# main.net
KiCad netlist of a schematic drawn in EAGLE
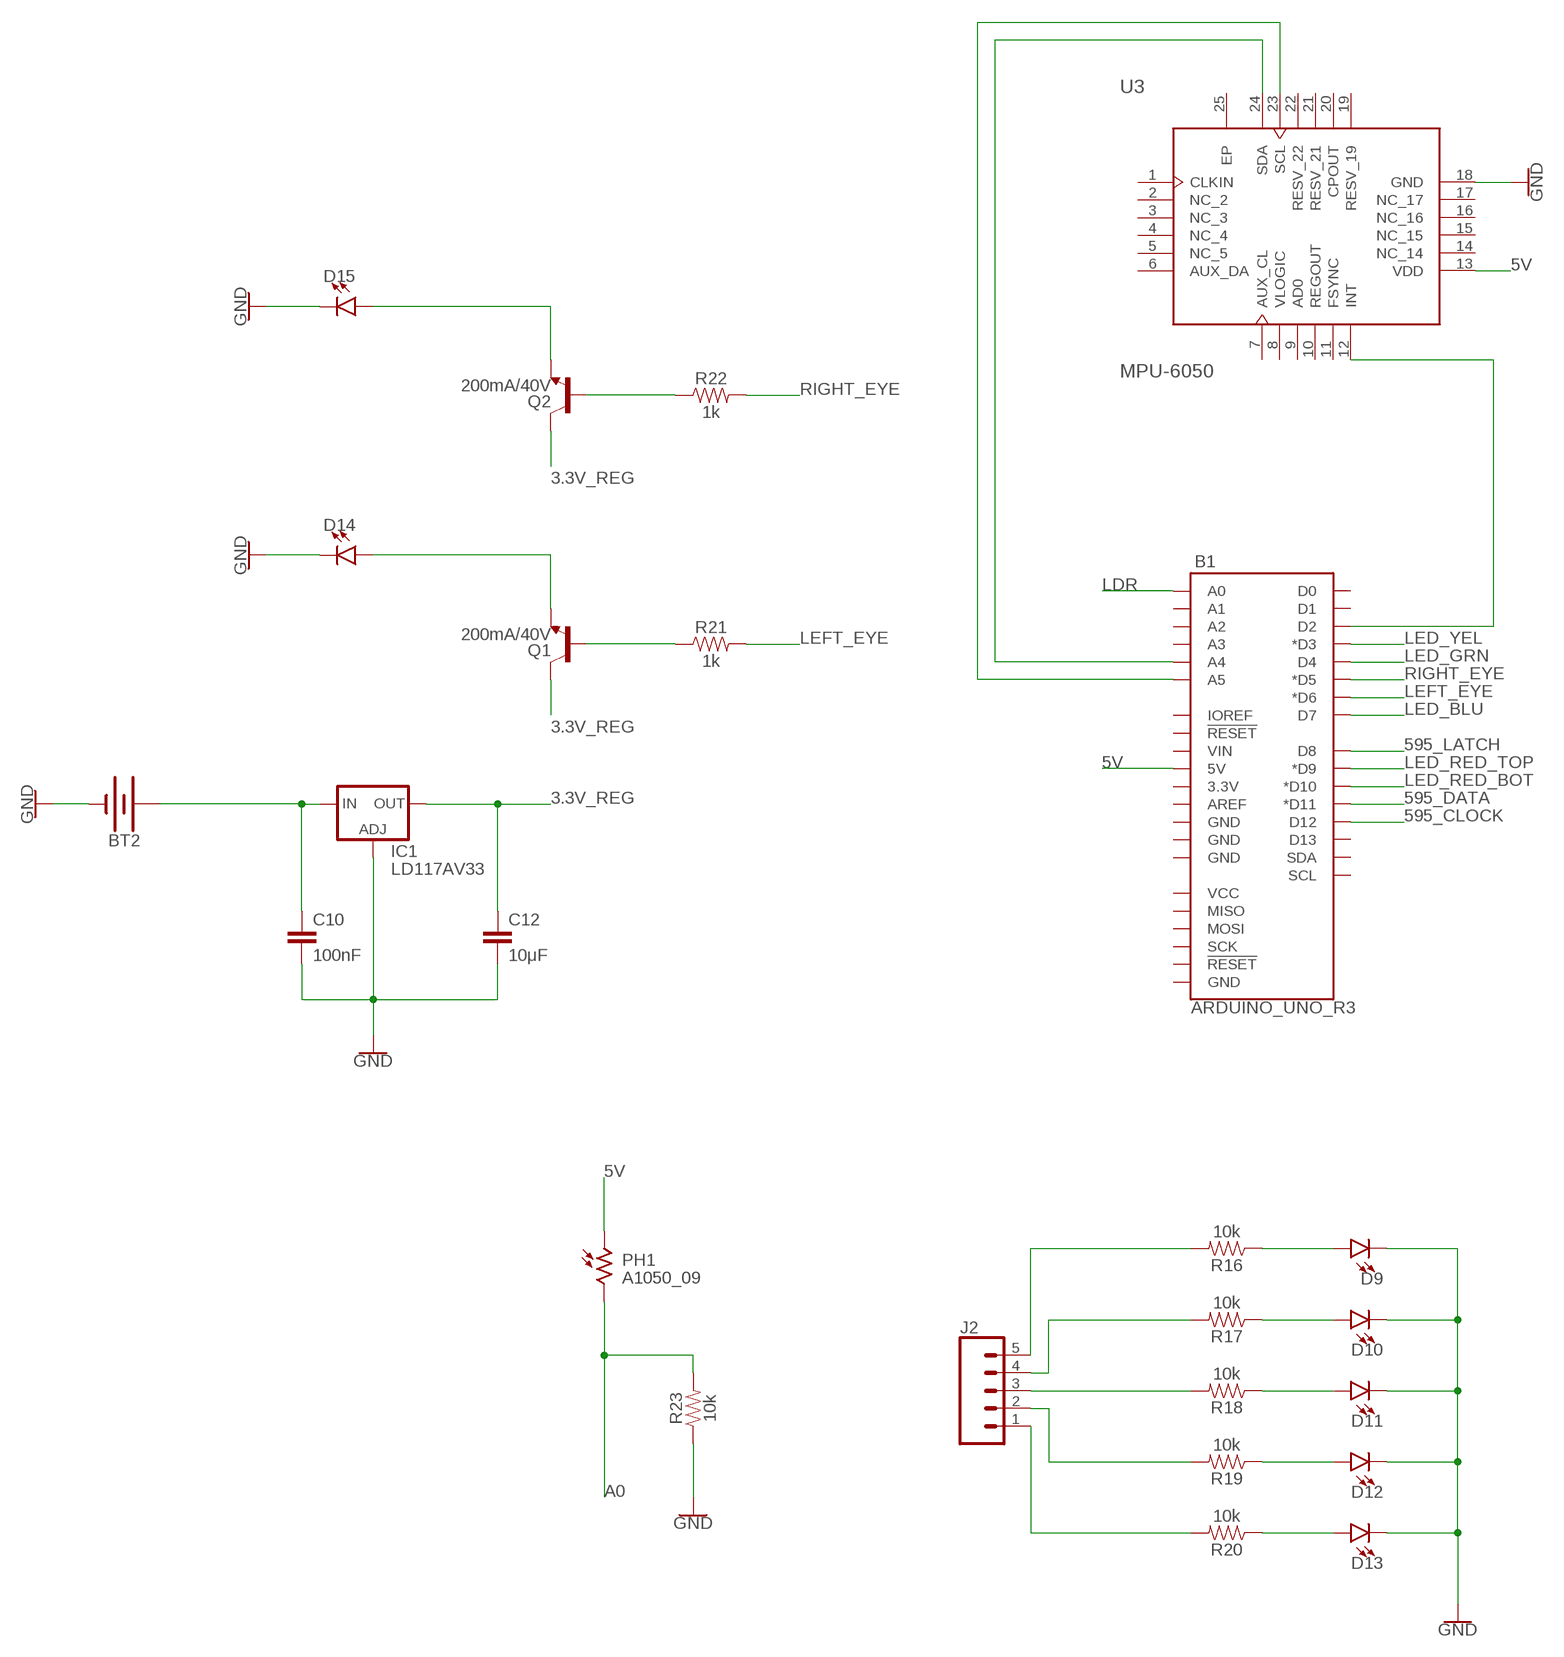
[diagram p0: schematic, sheet 1, part 1 of 2]
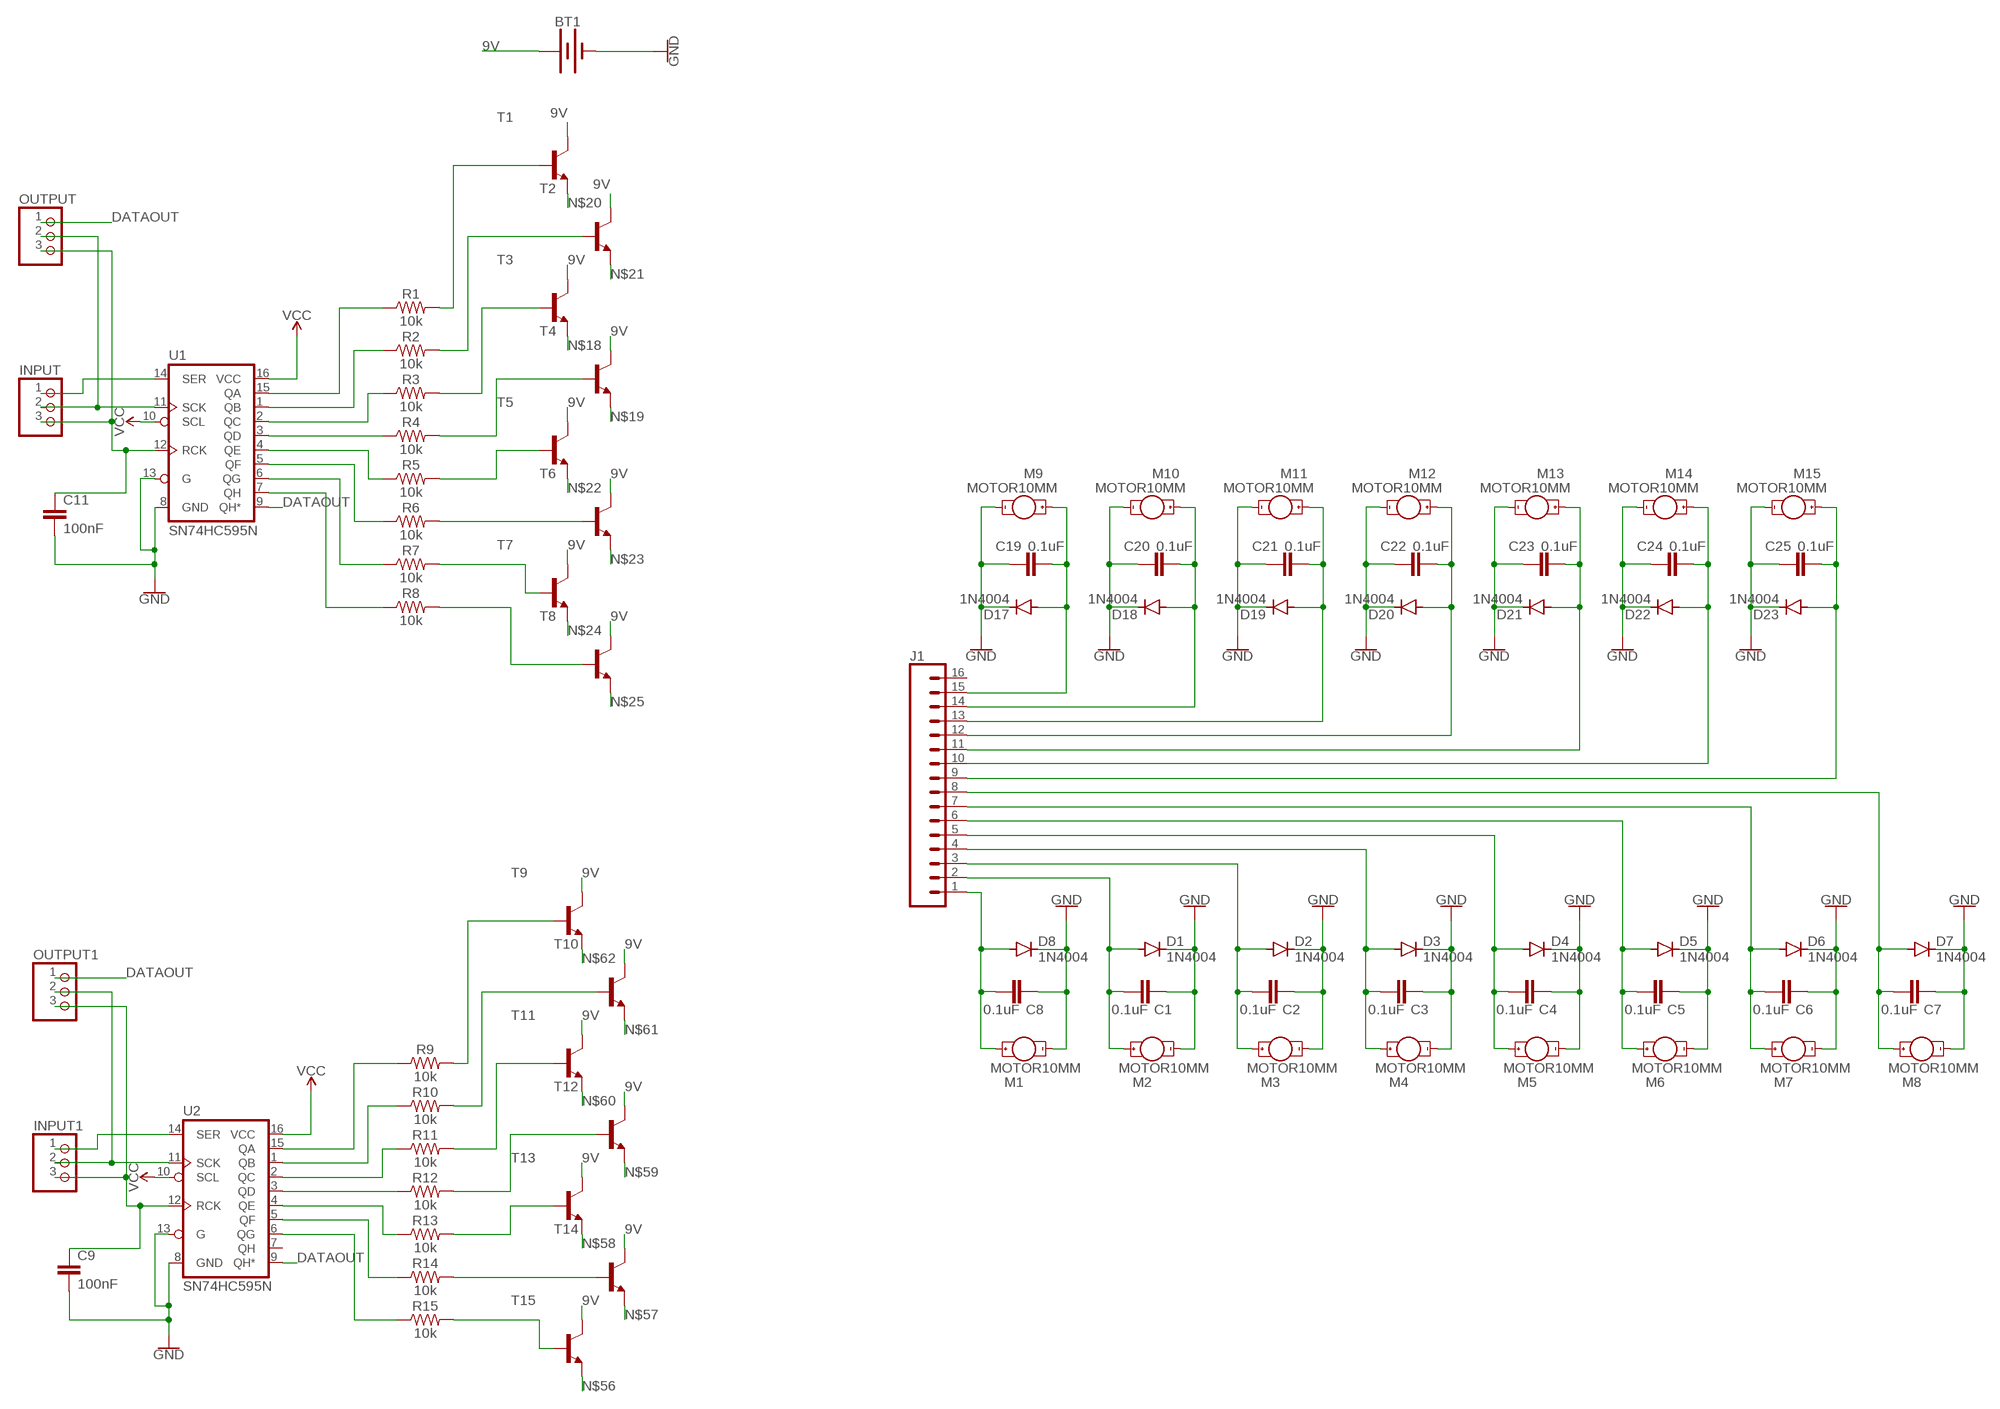
[diagram p1: schematic, sheet 1, part 2 of 2]

(export (version "E")
  (design (tool "Eeschema 10.0.6"))
  (components
    (comp (ref "B1")
      (value "ARDUINO_UNO_R3")
      (footprint "eagle-import:ARDUINO_R3")
      (libsource (lib "eagle-import") (part "ARDUINO_UNO_R3"))
    )
    (comp (ref "BT1")
      (value "BATTERY-9V")
      (footprint "eagle-import:BATTCON_9V")
      (libsource (lib "eagle-import") (part "BATTERY-9V"))
    )
    (comp (ref "BT2")
      (value "BATTERY-9V")
      (footprint "eagle-import:BATTCON_9V")
      (libsource (lib "eagle-import") (part "BATTERY-9V"))
    )
    (comp (ref "C1")
      (value "0.1uF")
      (footprint "eagle-import:CAP-PTH-SMALL-KIT")
      (libsource (lib "eagle-import") (part "0.1UF-KIT-EZ-50V-20%"))
    )
    (comp (ref "C2")
      (value "0.1uF")
      (footprint "eagle-import:CAP-PTH-SMALL-KIT")
      (libsource (lib "eagle-import") (part "0.1UF-KIT-EZ-50V-20%"))
    )
    (comp (ref "C3")
      (value "0.1uF")
      (footprint "eagle-import:CAP-PTH-SMALL-KIT")
      (libsource (lib "eagle-import") (part "0.1UF-KIT-EZ-50V-20%"))
    )
    (comp (ref "C4")
      (value "0.1uF")
      (footprint "eagle-import:CAP-PTH-SMALL-KIT")
      (libsource (lib "eagle-import") (part "0.1UF-KIT-EZ-50V-20%"))
    )
    (comp (ref "C5")
      (value "0.1uF")
      (footprint "eagle-import:CAP-PTH-SMALL-KIT")
      (libsource (lib "eagle-import") (part "0.1UF-KIT-EZ-50V-20%"))
    )
    (comp (ref "C6")
      (value "0.1uF")
      (footprint "eagle-import:CAP-PTH-SMALL-KIT")
      (libsource (lib "eagle-import") (part "0.1UF-KIT-EZ-50V-20%"))
    )
    (comp (ref "C7")
      (value "0.1uF")
      (footprint "eagle-import:CAP-PTH-SMALL-KIT")
      (libsource (lib "eagle-import") (part "0.1UF-KIT-EZ-50V-20%"))
    )
    (comp (ref "C8")
      (value "0.1uF")
      (footprint "eagle-import:CAP-PTH-SMALL-KIT")
      (libsource (lib "eagle-import") (part "0.1UF-KIT-EZ-50V-20%"))
    )
    (comp (ref "C9")
      (value "100nF")
      (footprint "eagle-import:CAP-PTH-10MM")
      (libsource (lib "eagle-import") (part "10NF-PTH-10MM-10000V-1-%"))
    )
    (comp (ref "C10")
      (value "100nF")
      (footprint "eagle-import:CAP-PTH-10MM")
      (libsource (lib "eagle-import") (part "10NF-PTH-10MM-10000V-1-%"))
    )
    (comp (ref "C11")
      (value "100nF")
      (footprint "eagle-import:CAP-PTH-10MM")
      (libsource (lib "eagle-import") (part "10NF-PTH-10MM-10000V-1-%"))
    )
    (comp (ref "C12")
      (value "10μF")
      (footprint "eagle-import:CAP-PTH-10MM")
      (libsource (lib "eagle-import") (part "10NF-PTH-10MM-10000V-1-%"))
    )
    (comp (ref "C19")
      (value "0.1uF")
      (footprint "eagle-import:CAP-PTH-SMALL-KIT")
      (libsource (lib "eagle-import") (part "0.1UF-KIT-EZ-50V-20%"))
    )
    (comp (ref "C20")
      (value "0.1uF")
      (footprint "eagle-import:CAP-PTH-SMALL-KIT")
      (libsource (lib "eagle-import") (part "0.1UF-KIT-EZ-50V-20%"))
    )
    (comp (ref "C21")
      (value "0.1uF")
      (footprint "eagle-import:CAP-PTH-SMALL-KIT")
      (libsource (lib "eagle-import") (part "0.1UF-KIT-EZ-50V-20%"))
    )
    (comp (ref "C22")
      (value "0.1uF")
      (footprint "eagle-import:CAP-PTH-SMALL-KIT")
      (libsource (lib "eagle-import") (part "0.1UF-KIT-EZ-50V-20%"))
    )
    (comp (ref "C23")
      (value "0.1uF")
      (footprint "eagle-import:CAP-PTH-SMALL-KIT")
      (libsource (lib "eagle-import") (part "0.1UF-KIT-EZ-50V-20%"))
    )
    (comp (ref "C24")
      (value "0.1uF")
      (footprint "eagle-import:CAP-PTH-SMALL-KIT")
      (libsource (lib "eagle-import") (part "0.1UF-KIT-EZ-50V-20%"))
    )
    (comp (ref "C25")
      (value "0.1uF")
      (footprint "eagle-import:CAP-PTH-SMALL-KIT")
      (libsource (lib "eagle-import") (part "0.1UF-KIT-EZ-50V-20%"))
    )
    (comp (ref "D1")
      (value "1N4004")
      (footprint "eagle-import:DO41-10")
      (libsource (lib "eagle-import") (part "1N4004"))
    )
    (comp (ref "D2")
      (value "1N4004")
      (footprint "eagle-import:DO41-10")
      (libsource (lib "eagle-import") (part "1N4004"))
    )
    (comp (ref "D3")
      (value "1N4004")
      (footprint "eagle-import:DO41-10")
      (libsource (lib "eagle-import") (part "1N4004"))
    )
    (comp (ref "D4")
      (value "1N4004")
      (footprint "eagle-import:DO41-10")
      (libsource (lib "eagle-import") (part "1N4004"))
    )
    (comp (ref "D5")
      (value "1N4004")
      (footprint "eagle-import:DO41-10")
      (libsource (lib "eagle-import") (part "1N4004"))
    )
    (comp (ref "D6")
      (value "1N4004")
      (footprint "eagle-import:DO41-10")
      (libsource (lib "eagle-import") (part "1N4004"))
    )
    (comp (ref "D7")
      (value "1N4004")
      (footprint "eagle-import:DO41-10")
      (libsource (lib "eagle-import") (part "1N4004"))
    )
    (comp (ref "D8")
      (value "1N4004")
      (footprint "eagle-import:DO41-10")
      (libsource (lib "eagle-import") (part "1N4004"))
    )
    (comp (ref "D9")
      (value "LED5MM")
      (footprint "eagle-import:LED_5MM")
      (libsource (lib "eagle-import") (part "LED5MM"))
    )
    (comp (ref "D10")
      (value "LED5MM")
      (footprint "eagle-import:LED_5MM")
      (libsource (lib "eagle-import") (part "LED5MM"))
    )
    (comp (ref "D11")
      (value "LED5MM")
      (footprint "eagle-import:LED_5MM")
      (libsource (lib "eagle-import") (part "LED5MM"))
    )
    (comp (ref "D12")
      (value "LED5MM")
      (footprint "eagle-import:LED_5MM")
      (libsource (lib "eagle-import") (part "LED5MM"))
    )
    (comp (ref "D13")
      (value "LED5MM")
      (footprint "eagle-import:LED_5MM")
      (libsource (lib "eagle-import") (part "LED5MM"))
    )
    (comp (ref "D14")
      (value "LED10MM")
      (footprint "eagle-import:LED_10MM")
      (libsource (lib "eagle-import") (part "LED10MM"))
    )
    (comp (ref "D15")
      (value "LED10MM")
      (footprint "eagle-import:LED_10MM")
      (libsource (lib "eagle-import") (part "LED10MM"))
    )
    (comp (ref "D17")
      (value "1N4004")
      (footprint "eagle-import:DO41-10")
      (libsource (lib "eagle-import") (part "1N4004"))
    )
    (comp (ref "D18")
      (value "1N4004")
      (footprint "eagle-import:DO41-10")
      (libsource (lib "eagle-import") (part "1N4004"))
    )
    (comp (ref "D19")
      (value "1N4004")
      (footprint "eagle-import:DO41-10")
      (libsource (lib "eagle-import") (part "1N4004"))
    )
    (comp (ref "D20")
      (value "1N4004")
      (footprint "eagle-import:DO41-10")
      (libsource (lib "eagle-import") (part "1N4004"))
    )
    (comp (ref "D21")
      (value "1N4004")
      (footprint "eagle-import:DO41-10")
      (libsource (lib "eagle-import") (part "1N4004"))
    )
    (comp (ref "D22")
      (value "1N4004")
      (footprint "eagle-import:DO41-10")
      (libsource (lib "eagle-import") (part "1N4004"))
    )
    (comp (ref "D23")
      (value "1N4004")
      (footprint "eagle-import:DO41-10")
      (libsource (lib "eagle-import") (part "1N4004"))
    )
    (comp (ref "IC1")
      (value "LD117AV33")
      (footprint "eagle-import:TO220L1")
      (libsource (lib "eagle-import") (part "LD117A?V33"))
    )
    (comp (ref "INPUT")
      (value "PINHD-1X3")
      (footprint "eagle-import:1X03")
      (libsource (lib "eagle-import") (part "PINHD-1X3"))
    )
    (comp (ref "INPUT1")
      (value "PINHD-1X3")
      (footprint "eagle-import:1X03")
      (libsource (lib "eagle-import") (part "PINHD-1X3"))
    )
    (comp (ref "J1")
      (value "CONN_16")
      (footprint "eagle-import:1X16")
      (libsource (lib "eagle-import") (part "CONN_16"))
    )
    (comp (ref "J2")
      (value "CONN_05")
      (footprint "eagle-import:1X05")
      (libsource (lib "eagle-import") (part "CONN_05"))
    )
    (comp (ref "M1")
      (value "MOTOR10MM")
      (footprint "eagle-import:VIBE-MOTOR-10MM")
      (libsource (lib "eagle-import") (part "MOTOR10MM"))
    )
    (comp (ref "M2")
      (value "MOTOR10MM")
      (footprint "eagle-import:VIBE-MOTOR-10MM")
      (libsource (lib "eagle-import") (part "MOTOR10MM"))
    )
    (comp (ref "M3")
      (value "MOTOR10MM")
      (footprint "eagle-import:VIBE-MOTOR-10MM")
      (libsource (lib "eagle-import") (part "MOTOR10MM"))
    )
    (comp (ref "M4")
      (value "MOTOR10MM")
      (footprint "eagle-import:VIBE-MOTOR-10MM")
      (libsource (lib "eagle-import") (part "MOTOR10MM"))
    )
    (comp (ref "M5")
      (value "MOTOR10MM")
      (footprint "eagle-import:VIBE-MOTOR-10MM")
      (libsource (lib "eagle-import") (part "MOTOR10MM"))
    )
    (comp (ref "M6")
      (value "MOTOR10MM")
      (footprint "eagle-import:VIBE-MOTOR-10MM")
      (libsource (lib "eagle-import") (part "MOTOR10MM"))
    )
    (comp (ref "M7")
      (value "MOTOR10MM")
      (footprint "eagle-import:VIBE-MOTOR-10MM")
      (libsource (lib "eagle-import") (part "MOTOR10MM"))
    )
    (comp (ref "M8")
      (value "MOTOR10MM")
      (footprint "eagle-import:VIBE-MOTOR-10MM")
      (libsource (lib "eagle-import") (part "MOTOR10MM"))
    )
    (comp (ref "M9")
      (value "MOTOR10MM")
      (footprint "eagle-import:VIBE-MOTOR-10MM")
      (libsource (lib "eagle-import") (part "MOTOR10MM"))
    )
    (comp (ref "M10")
      (value "MOTOR10MM")
      (footprint "eagle-import:VIBE-MOTOR-10MM")
      (libsource (lib "eagle-import") (part "MOTOR10MM"))
    )
    (comp (ref "M11")
      (value "MOTOR10MM")
      (footprint "eagle-import:VIBE-MOTOR-10MM")
      (libsource (lib "eagle-import") (part "MOTOR10MM"))
    )
    (comp (ref "M12")
      (value "MOTOR10MM")
      (footprint "eagle-import:VIBE-MOTOR-10MM")
      (libsource (lib "eagle-import") (part "MOTOR10MM"))
    )
    (comp (ref "M13")
      (value "MOTOR10MM")
      (footprint "eagle-import:VIBE-MOTOR-10MM")
      (libsource (lib "eagle-import") (part "MOTOR10MM"))
    )
    (comp (ref "M14")
      (value "MOTOR10MM")
      (footprint "eagle-import:VIBE-MOTOR-10MM")
      (libsource (lib "eagle-import") (part "MOTOR10MM"))
    )
    (comp (ref "M15")
      (value "MOTOR10MM")
      (footprint "eagle-import:VIBE-MOTOR-10MM")
      (libsource (lib "eagle-import") (part "MOTOR10MM"))
    )
    (comp (ref "OUTPUT")
      (value "PINHD-1X3")
      (footprint "eagle-import:1X03")
      (libsource (lib "eagle-import") (part "PINHD-1X3"))
    )
    (comp (ref "OUTPUT1")
      (value "PINHD-1X3")
      (footprint "eagle-import:1X03")
      (libsource (lib "eagle-import") (part "PINHD-1X3"))
    )
    (comp (ref "PH1")
      (value "A1050_09")
      (footprint "eagle-import:T0-46-A10XX")
      (libsource (lib "eagle-import") (part "A1050_09"))
    )
    (comp (ref "Q1")
      (value "200mA/40V")
      (footprint "eagle-import:TO-92")
      (libsource (lib "eagle-import") (part "TRANS_NPN-2N3904"))
    )
    (comp (ref "Q2")
      (value "200mA/40V")
      (footprint "eagle-import:TO-92")
      (libsource (lib "eagle-import") (part "TRANS_NPN-2N3904"))
    )
    (comp (ref "R1")
      (value "10k")
      (footprint "eagle-import:AXIAL-0.3")
      (libsource (lib "eagle-import") (part "10KOHM-HORIZ-1/4W-1%"))
    )
    (comp (ref "R2")
      (value "10k")
      (footprint "eagle-import:AXIAL-0.3")
      (libsource (lib "eagle-import") (part "10KOHM-HORIZ-1/4W-1%"))
    )
    (comp (ref "R3")
      (value "10k")
      (footprint "eagle-import:AXIAL-0.3")
      (libsource (lib "eagle-import") (part "10KOHM-HORIZ-1/4W-1%"))
    )
    (comp (ref "R4")
      (value "10k")
      (footprint "eagle-import:AXIAL-0.3")
      (libsource (lib "eagle-import") (part "10KOHM-HORIZ-1/4W-1%"))
    )
    (comp (ref "R5")
      (value "10k")
      (footprint "eagle-import:AXIAL-0.3")
      (libsource (lib "eagle-import") (part "10KOHM-HORIZ-1/4W-1%"))
    )
    (comp (ref "R6")
      (value "10k")
      (footprint "eagle-import:AXIAL-0.3")
      (libsource (lib "eagle-import") (part "10KOHM-HORIZ-1/4W-1%"))
    )
    (comp (ref "R7")
      (value "10k")
      (footprint "eagle-import:AXIAL-0.3")
      (libsource (lib "eagle-import") (part "10KOHM-HORIZ-1/4W-1%"))
    )
    (comp (ref "R8")
      (value "10k")
      (footprint "eagle-import:AXIAL-0.3")
      (libsource (lib "eagle-import") (part "10KOHM-HORIZ-1/4W-1%"))
    )
    (comp (ref "R9")
      (value "10k")
      (footprint "eagle-import:AXIAL-0.3")
      (libsource (lib "eagle-import") (part "10KOHM-HORIZ-1/4W-1%"))
    )
    (comp (ref "R10")
      (value "10k")
      (footprint "eagle-import:AXIAL-0.3")
      (libsource (lib "eagle-import") (part "10KOHM-HORIZ-1/4W-1%"))
    )
    (comp (ref "R11")
      (value "10k")
      (footprint "eagle-import:AXIAL-0.3")
      (libsource (lib "eagle-import") (part "10KOHM-HORIZ-1/4W-1%"))
    )
    (comp (ref "R12")
      (value "10k")
      (footprint "eagle-import:AXIAL-0.3")
      (libsource (lib "eagle-import") (part "10KOHM-HORIZ-1/4W-1%"))
    )
    (comp (ref "R13")
      (value "10k")
      (footprint "eagle-import:AXIAL-0.3")
      (libsource (lib "eagle-import") (part "10KOHM-HORIZ-1/4W-1%"))
    )
    (comp (ref "R14")
      (value "10k")
      (footprint "eagle-import:AXIAL-0.3")
      (libsource (lib "eagle-import") (part "10KOHM-HORIZ-1/4W-1%"))
    )
    (comp (ref "R15")
      (value "10k")
      (footprint "eagle-import:AXIAL-0.3")
      (libsource (lib "eagle-import") (part "10KOHM-HORIZ-1/4W-1%"))
    )
    (comp (ref "R16")
      (value "10k")
      (footprint "eagle-import:AXIAL-0.3")
      (libsource (lib "eagle-import") (part "10KOHM-HORIZ-1/4W-1%"))
    )
    (comp (ref "R17")
      (value "10k")
      (footprint "eagle-import:AXIAL-0.3")
      (libsource (lib "eagle-import") (part "10KOHM-HORIZ-1/4W-1%"))
    )
    (comp (ref "R18")
      (value "10k")
      (footprint "eagle-import:AXIAL-0.3")
      (libsource (lib "eagle-import") (part "10KOHM-HORIZ-1/4W-1%"))
    )
    (comp (ref "R19")
      (value "10k")
      (footprint "eagle-import:AXIAL-0.3")
      (libsource (lib "eagle-import") (part "10KOHM-HORIZ-1/4W-1%"))
    )
    (comp (ref "R20")
      (value "10k")
      (footprint "eagle-import:AXIAL-0.3")
      (libsource (lib "eagle-import") (part "10KOHM-HORIZ-1/4W-1%"))
    )
    (comp (ref "R21")
      (value "1k")
      (footprint "eagle-import:AXIAL-0.3")
      (libsource (lib "eagle-import") (part "1KOHM-HORIZ-1/4W-1%"))
    )
    (comp (ref "R22")
      (value "1k")
      (footprint "eagle-import:AXIAL-0.3")
      (libsource (lib "eagle-import") (part "1KOHM-HORIZ-1/4W-1%"))
    )
    (comp (ref "R23")
      (value "10k")
      (footprint "eagle-import:AXIAL-0.3")
      (libsource (lib "eagle-import") (part "10KOHM-HORIZ-1/4W-1%"))
    )
    (comp (ref "T1")
      (value "2N3904-NPN-TO92-EBC")
      (footprint "eagle-import:TO92-EBC")
      (libsource (lib "eagle-import") (part "-NPN-TO92-EBC2N3904"))
    )
    (comp (ref "T2")
      (value "2N3904-NPN-TO92-EBC")
      (footprint "eagle-import:TO92-EBC")
      (libsource (lib "eagle-import") (part "-NPN-TO92-EBC2N3904"))
    )
    (comp (ref "T3")
      (value "2N3904-NPN-TO92-EBC")
      (footprint "eagle-import:TO92-EBC")
      (libsource (lib "eagle-import") (part "-NPN-TO92-EBC2N3904"))
    )
    (comp (ref "T4")
      (value "2N3904-NPN-TO92-EBC")
      (footprint "eagle-import:TO92-EBC")
      (libsource (lib "eagle-import") (part "-NPN-TO92-EBC2N3904"))
    )
    (comp (ref "T5")
      (value "2N3904-NPN-TO92-EBC")
      (footprint "eagle-import:TO92-EBC")
      (libsource (lib "eagle-import") (part "-NPN-TO92-EBC2N3904"))
    )
    (comp (ref "T6")
      (value "2N3904-NPN-TO92-EBC")
      (footprint "eagle-import:TO92-EBC")
      (libsource (lib "eagle-import") (part "-NPN-TO92-EBC2N3904"))
    )
    (comp (ref "T7")
      (value "2N3904-NPN-TO92-EBC")
      (footprint "eagle-import:TO92-EBC")
      (libsource (lib "eagle-import") (part "-NPN-TO92-EBC2N3904"))
    )
    (comp (ref "T8")
      (value "2N3904-NPN-TO92-EBC")
      (footprint "eagle-import:TO92-EBC")
      (libsource (lib "eagle-import") (part "-NPN-TO92-EBC2N3904"))
    )
    (comp (ref "T9")
      (value "2N3904-NPN-TO92-EBC")
      (footprint "eagle-import:TO92-EBC")
      (libsource (lib "eagle-import") (part "-NPN-TO92-EBC2N3904"))
    )
    (comp (ref "T10")
      (value "2N3904-NPN-TO92-EBC")
      (footprint "eagle-import:TO92-EBC")
      (libsource (lib "eagle-import") (part "-NPN-TO92-EBC2N3904"))
    )
    (comp (ref "T11")
      (value "2N3904-NPN-TO92-EBC")
      (footprint "eagle-import:TO92-EBC")
      (libsource (lib "eagle-import") (part "-NPN-TO92-EBC2N3904"))
    )
    (comp (ref "T12")
      (value "2N3904-NPN-TO92-EBC")
      (footprint "eagle-import:TO92-EBC")
      (libsource (lib "eagle-import") (part "-NPN-TO92-EBC2N3904"))
    )
    (comp (ref "T13")
      (value "2N3904-NPN-TO92-EBC")
      (footprint "eagle-import:TO92-EBC")
      (libsource (lib "eagle-import") (part "-NPN-TO92-EBC2N3904"))
    )
    (comp (ref "T14")
      (value "2N3904-NPN-TO92-EBC")
      (footprint "eagle-import:TO92-EBC")
      (libsource (lib "eagle-import") (part "-NPN-TO92-EBC2N3904"))
    )
    (comp (ref "T15")
      (value "2N3904-NPN-TO92-EBC")
      (footprint "eagle-import:TO92-EBC")
      (libsource (lib "eagle-import") (part "-NPN-TO92-EBC2N3904"))
    )
    (comp (ref "U1")
      (value "SN74HC595N")
      (footprint "eagle-import:DIP16")
      (libsource (lib "eagle-import") (part "74595NHC"))
    )
    (comp (ref "U2")
      (value "SN74HC595N")
      (footprint "eagle-import:DIP16")
      (libsource (lib "eagle-import") (part "74595NHC"))
    )
    (comp (ref "U3")
      (value "MPU-6050")
      (footprint "eagle-import:24-VFQFN")
      (fields
        (field (name "DIGIKEY_PART_NUMBER") "1428-1007-1-ND")
        (field (name "MANUFACTURER") "TDK InvenSense")
        (field (name "CREATED_BY") "PCBLayout.com")
      )
      (libsource (lib "eagle-import") (part "MPU-6050"))
    )
  )
  (nets
    (net (code "1") (name "/3.3V_REG") (class "Default")
      (node (ref "C12") (pin "1") (pinfunction "1_1") (pintype "passive"))
      (node (ref "IC1") (pin "2") (pinfunction "OUT_2") (pintype "passive"))
      (node (ref "Q1") (pin "3") (pinfunction "C_3") (pintype "passive"))
      (node (ref "Q2") (pin "3") (pinfunction "C_3") (pintype "passive"))
    )
    (net (code "2") (name "/5V") (class "Default")
      (node (ref "B1") (pin "5V") (pinfunction "5V_5V") (pintype "bidirectional"))
      (node (ref "PH1") (pin "1") (pinfunction "1_1") (pintype "passive"))
      (node (ref "U3") (pin "13") (pinfunction "VDD_13") (pintype "power_in"))
    )
    (net (code "3") (name "/9V") (class "Default")
      (node (ref "BT1") (pin "+") (pinfunction "+_+") (pintype "power_in"))
      (node (ref "T1") (pin "C") (pinfunction "C_C") (pintype "passive"))
      (node (ref "T10") (pin "C") (pinfunction "C_C") (pintype "passive"))
      (node (ref "T11") (pin "C") (pinfunction "C_C") (pintype "passive"))
      (node (ref "T12") (pin "C") (pinfunction "C_C") (pintype "passive"))
      (node (ref "T13") (pin "C") (pinfunction "C_C") (pintype "passive"))
      (node (ref "T14") (pin "C") (pinfunction "C_C") (pintype "passive"))
      (node (ref "T15") (pin "C") (pinfunction "C_C") (pintype "passive"))
      (node (ref "T2") (pin "C") (pinfunction "C_C") (pintype "passive"))
      (node (ref "T3") (pin "C") (pinfunction "C_C") (pintype "passive"))
      (node (ref "T4") (pin "C") (pinfunction "C_C") (pintype "passive"))
      (node (ref "T5") (pin "C") (pinfunction "C_C") (pintype "passive"))
      (node (ref "T6") (pin "C") (pinfunction "C_C") (pintype "passive"))
      (node (ref "T7") (pin "C") (pinfunction "C_C") (pintype "passive"))
      (node (ref "T8") (pin "C") (pinfunction "C_C") (pintype "passive"))
      (node (ref "T9") (pin "C") (pinfunction "C_C") (pintype "passive"))
    )
    (net (code "4") (name "/595_CLOCK") (class "Default")
      (node (ref "B1") (pin "D12") (pinfunction "D12_D12") (pintype "bidirectional"))
    )
    (net (code "5") (name "/595_DATA") (class "Default")
      (node (ref "B1") (pin "D11") (pinfunction "*D11_D11") (pintype "bidirectional"))
    )
    (net (code "6") (name "/595_LATCH") (class "Default")
      (node (ref "B1") (pin "D8") (pinfunction "D8_D8") (pintype "bidirectional"))
    )
    (net (code "7") (name "/A0") (class "Default")
      (node (ref "PH1") (pin "2") (pinfunction "2_2") (pintype "passive"))
      (node (ref "R23") (pin "P$2") (pinfunction "2_P$2") (pintype "passive"))
    )
    (net (code "8") (name "/DATAOUT") (class "Default")
      (node (ref "OUTPUT") (pin "1") (pinfunction "1_1") (pintype "passive"))
      (node (ref "OUTPUT1") (pin "1") (pinfunction "1_1") (pintype "passive"))
      (node (ref "U1") (pin "9") (pinfunction "QH*_9") (pintype "tri_state"))
      (node (ref "U2") (pin "9") (pinfunction "QH*_9") (pintype "tri_state"))
    )
    (net (code "9") (name "/EP") (class "Default")
      (node (ref "U3") (pin "25") (pinfunction "EP_25") (pintype "power_in"))
    )
    (net (code "10") (name "/LDR") (class "Default")
      (node (ref "B1") (pin "A0") (pinfunction "A0_A0") (pintype "bidirectional"))
    )
    (net (code "11") (name "/LED_BLU") (class "Default")
      (node (ref "B1") (pin "D7") (pinfunction "D7_D7") (pintype "bidirectional"))
    )
    (net (code "12") (name "/LED_GRN") (class "Default")
      (node (ref "B1") (pin "D4") (pinfunction "D4_D4") (pintype "bidirectional"))
    )
    (net (code "13") (name "/LED_RED_BOT") (class "Default")
      (node (ref "B1") (pin "D10") (pinfunction "*D10_D10") (pintype "bidirectional"))
    )
    (net (code "14") (name "/LED_RED_TOP") (class "Default")
      (node (ref "B1") (pin "D9") (pinfunction "*D9_D9") (pintype "bidirectional"))
    )
    (net (code "15") (name "/LED_YEL") (class "Default")
      (node (ref "B1") (pin "D3") (pinfunction "*D3_D3") (pintype "bidirectional"))
    )
    (net (code "16") (name "/LEFT_EYE") (class "Default")
      (node (ref "B1") (pin "D6") (pinfunction "*D6_D6") (pintype "bidirectional"))
      (node (ref "R21") (pin "P$2") (pinfunction "2_P$2") (pintype "passive"))
    )
    (net (code "17") (name "/N$18") (class "Default")
      (node (ref "C2") (pin "2") (pinfunction "2_2") (pintype "passive"))
      (node (ref "D2") (pin "A") (pinfunction "A_A") (pintype "passive"))
      (node (ref "J1") (pin "3") (pinfunction "3_3") (pintype "passive"))
      (node (ref "M3") (pin "+") (pinfunction "+_+") (pintype "bidirectional"))
      (node (ref "T3") (pin "E") (pinfunction "E_E") (pintype "passive"))
    )
    (net (code "18") (name "/N$19") (class "Default")
      (node (ref "C3") (pin "2") (pinfunction "2_2") (pintype "passive"))
      (node (ref "D3") (pin "A") (pinfunction "A_A") (pintype "passive"))
      (node (ref "J1") (pin "4") (pinfunction "4_4") (pintype "passive"))
      (node (ref "M4") (pin "+") (pinfunction "+_+") (pintype "bidirectional"))
      (node (ref "T4") (pin "E") (pinfunction "E_E") (pintype "passive"))
    )
    (net (code "19") (name "/N$20") (class "Default")
      (node (ref "C8") (pin "2") (pinfunction "2_2") (pintype "passive"))
      (node (ref "D8") (pin "A") (pinfunction "A_A") (pintype "passive"))
      (node (ref "J1") (pin "1") (pinfunction "1_1") (pintype "passive"))
      (node (ref "M1") (pin "+") (pinfunction "+_+") (pintype "bidirectional"))
      (node (ref "T1") (pin "E") (pinfunction "E_E") (pintype "passive"))
    )
    (net (code "20") (name "/N$21") (class "Default")
      (node (ref "C1") (pin "2") (pinfunction "2_2") (pintype "passive"))
      (node (ref "D1") (pin "A") (pinfunction "A_A") (pintype "passive"))
      (node (ref "J1") (pin "2") (pinfunction "2_2") (pintype "passive"))
      (node (ref "M2") (pin "+") (pinfunction "+_+") (pintype "bidirectional"))
      (node (ref "T2") (pin "E") (pinfunction "E_E") (pintype "passive"))
    )
    (net (code "21") (name "/N$22") (class "Default")
      (node (ref "C4") (pin "2") (pinfunction "2_2") (pintype "passive"))
      (node (ref "D4") (pin "A") (pinfunction "A_A") (pintype "passive"))
      (node (ref "J1") (pin "5") (pinfunction "5_5") (pintype "passive"))
      (node (ref "M5") (pin "+") (pinfunction "+_+") (pintype "bidirectional"))
      (node (ref "T5") (pin "E") (pinfunction "E_E") (pintype "passive"))
    )
    (net (code "22") (name "/N$23") (class "Default")
      (node (ref "C5") (pin "2") (pinfunction "2_2") (pintype "passive"))
      (node (ref "D5") (pin "A") (pinfunction "A_A") (pintype "passive"))
      (node (ref "J1") (pin "6") (pinfunction "6_6") (pintype "passive"))
      (node (ref "M6") (pin "+") (pinfunction "+_+") (pintype "bidirectional"))
      (node (ref "T6") (pin "E") (pinfunction "E_E") (pintype "passive"))
    )
    (net (code "23") (name "/N$24") (class "Default")
      (node (ref "C6") (pin "2") (pinfunction "2_2") (pintype "passive"))
      (node (ref "D6") (pin "A") (pinfunction "A_A") (pintype "passive"))
      (node (ref "J1") (pin "7") (pinfunction "7_7") (pintype "passive"))
      (node (ref "M7") (pin "+") (pinfunction "+_+") (pintype "bidirectional"))
      (node (ref "T7") (pin "E") (pinfunction "E_E") (pintype "passive"))
    )
    (net (code "24") (name "/N$25") (class "Default")
      (node (ref "C7") (pin "2") (pinfunction "2_2") (pintype "passive"))
      (node (ref "D7") (pin "A") (pinfunction "A_A") (pintype "passive"))
      (node (ref "J1") (pin "8") (pinfunction "8_8") (pintype "passive"))
      (node (ref "M8") (pin "+") (pinfunction "+_+") (pintype "bidirectional"))
      (node (ref "T8") (pin "E") (pinfunction "E_E") (pintype "passive"))
    )
    (net (code "25") (name "/N$56") (class "Default")
      (node (ref "C19") (pin "2") (pinfunction "2_2") (pintype "passive"))
      (node (ref "D17") (pin "A") (pinfunction "A_A") (pintype "passive"))
      (node (ref "J1") (pin "15") (pinfunction "15_15") (pintype "passive"))
      (node (ref "M9") (pin "+") (pinfunction "+_+") (pintype "bidirectional"))
      (node (ref "T15") (pin "E") (pinfunction "E_E") (pintype "passive"))
    )
    (net (code "26") (name "/N$57") (class "Default")
      (node (ref "C20") (pin "2") (pinfunction "2_2") (pintype "passive"))
      (node (ref "D18") (pin "A") (pinfunction "A_A") (pintype "passive"))
      (node (ref "J1") (pin "14") (pinfunction "14_14") (pintype "passive"))
      (node (ref "M10") (pin "+") (pinfunction "+_+") (pintype "bidirectional"))
      (node (ref "T14") (pin "E") (pinfunction "E_E") (pintype "passive"))
    )
    (net (code "27") (name "/N$58") (class "Default")
      (node (ref "C21") (pin "2") (pinfunction "2_2") (pintype "passive"))
      (node (ref "D19") (pin "A") (pinfunction "A_A") (pintype "passive"))
      (node (ref "J1") (pin "13") (pinfunction "13_13") (pintype "passive"))
      (node (ref "M11") (pin "+") (pinfunction "+_+") (pintype "bidirectional"))
      (node (ref "T13") (pin "E") (pinfunction "E_E") (pintype "passive"))
    )
    (net (code "28") (name "/N$59") (class "Default")
      (node (ref "C22") (pin "2") (pinfunction "2_2") (pintype "passive"))
      (node (ref "D20") (pin "A") (pinfunction "A_A") (pintype "passive"))
      (node (ref "J1") (pin "12") (pinfunction "12_12") (pintype "passive"))
      (node (ref "M12") (pin "+") (pinfunction "+_+") (pintype "bidirectional"))
      (node (ref "T12") (pin "E") (pinfunction "E_E") (pintype "passive"))
    )
    (net (code "29") (name "/N$60") (class "Default")
      (node (ref "C23") (pin "2") (pinfunction "2_2") (pintype "passive"))
      (node (ref "D21") (pin "A") (pinfunction "A_A") (pintype "passive"))
      (node (ref "J1") (pin "11") (pinfunction "11_11") (pintype "passive"))
      (node (ref "M13") (pin "+") (pinfunction "+_+") (pintype "bidirectional"))
      (node (ref "T11") (pin "E") (pinfunction "E_E") (pintype "passive"))
    )
    (net (code "30") (name "/N$61") (class "Default")
      (node (ref "C24") (pin "2") (pinfunction "2_2") (pintype "passive"))
      (node (ref "D22") (pin "A") (pinfunction "A_A") (pintype "passive"))
      (node (ref "J1") (pin "10") (pinfunction "10_10") (pintype "passive"))
      (node (ref "M14") (pin "+") (pinfunction "+_+") (pintype "bidirectional"))
      (node (ref "T10") (pin "E") (pinfunction "E_E") (pintype "passive"))
    )
    (net (code "31") (name "/N$62") (class "Default")
      (node (ref "C25") (pin "2") (pinfunction "2_2") (pintype "passive"))
      (node (ref "D23") (pin "A") (pinfunction "A_A") (pintype "passive"))
      (node (ref "J1") (pin "9") (pinfunction "9_9") (pintype "passive"))
      (node (ref "M15") (pin "+") (pinfunction "+_+") (pintype "bidirectional"))
      (node (ref "T9") (pin "E") (pinfunction "E_E") (pintype "passive"))
    )
    (net (code "32") (name "/RIGHT_EYE") (class "Default")
      (node (ref "B1") (pin "D5") (pinfunction "*D5_D5") (pintype "bidirectional"))
      (node (ref "R22") (pin "P$2") (pinfunction "2_P$2") (pintype "passive"))
    )
    (net (code "33") (name "/VLOGIC") (class "Default")
      (node (ref "U3") (pin "8") (pinfunction "VLOGIC_8") (pintype "power_in"))
    )
    (net (code "34") (name "GND") (class "Default")
      (node (ref "BT1") (pin "-") (pinfunction "-_-") (pintype "power_in"))
      (node (ref "BT2") (pin "-") (pinfunction "-_-") (pintype "power_in"))
      (node (ref "C1") (pin "1") (pinfunction "1_1") (pintype "passive"))
      (node (ref "C10") (pin "2") (pinfunction "2_2") (pintype "passive"))
      (node (ref "C11") (pin "2") (pinfunction "2_2") (pintype "passive"))
      (node (ref "C12") (pin "2") (pinfunction "2_2") (pintype "passive"))
      (node (ref "C19") (pin "1") (pinfunction "1_1") (pintype "passive"))
      (node (ref "C2") (pin "1") (pinfunction "1_1") (pintype "passive"))
      (node (ref "C20") (pin "1") (pinfunction "1_1") (pintype "passive"))
      (node (ref "C21") (pin "1") (pinfunction "1_1") (pintype "passive"))
      (node (ref "C22") (pin "1") (pinfunction "1_1") (pintype "passive"))
      (node (ref "C23") (pin "1") (pinfunction "1_1") (pintype "passive"))
      (node (ref "C24") (pin "1") (pinfunction "1_1") (pintype "passive"))
      (node (ref "C25") (pin "1") (pinfunction "1_1") (pintype "passive"))
      (node (ref "C3") (pin "1") (pinfunction "1_1") (pintype "passive"))
      (node (ref "C4") (pin "1") (pinfunction "1_1") (pintype "passive"))
      (node (ref "C5") (pin "1") (pinfunction "1_1") (pintype "passive"))
      (node (ref "C6") (pin "1") (pinfunction "1_1") (pintype "passive"))
      (node (ref "C7") (pin "1") (pinfunction "1_1") (pintype "passive"))
      (node (ref "C8") (pin "1") (pinfunction "1_1") (pintype "passive"))
      (node (ref "C9") (pin "2") (pinfunction "2_2") (pintype "passive"))
      (node (ref "D1") (pin "C") (pinfunction "C_C") (pintype "passive"))
      (node (ref "D10") (pin "K") (pinfunction "C_K") (pintype "passive"))
      (node (ref "D11") (pin "K") (pinfunction "C_K") (pintype "passive"))
      (node (ref "D12") (pin "K") (pinfunction "C_K") (pintype "passive"))
      (node (ref "D13") (pin "K") (pinfunction "C_K") (pintype "passive"))
      (node (ref "D14") (pin "C") (pinfunction "C_C") (pintype "passive"))
      (node (ref "D15") (pin "C") (pinfunction "C_C") (pintype "passive"))
      (node (ref "D17") (pin "C") (pinfunction "C_C") (pintype "passive"))
      (node (ref "D18") (pin "C") (pinfunction "C_C") (pintype "passive"))
      (node (ref "D19") (pin "C") (pinfunction "C_C") (pintype "passive"))
      (node (ref "D2") (pin "C") (pinfunction "C_C") (pintype "passive"))
      (node (ref "D20") (pin "C") (pinfunction "C_C") (pintype "passive"))
      (node (ref "D21") (pin "C") (pinfunction "C_C") (pintype "passive"))
      (node (ref "D22") (pin "C") (pinfunction "C_C") (pintype "passive"))
      (node (ref "D23") (pin "C") (pinfunction "C_C") (pintype "passive"))
      (node (ref "D3") (pin "C") (pinfunction "C_C") (pintype "passive"))
      (node (ref "D4") (pin "C") (pinfunction "C_C") (pintype "passive"))
      (node (ref "D5") (pin "C") (pinfunction "C_C") (pintype "passive"))
      (node (ref "D6") (pin "C") (pinfunction "C_C") (pintype "passive"))
      (node (ref "D7") (pin "C") (pinfunction "C_C") (pintype "passive"))
      (node (ref "D8") (pin "C") (pinfunction "C_C") (pintype "passive"))
      (node (ref "D9") (pin "K") (pinfunction "C_K") (pintype "passive"))
      (node (ref "IC1") (pin "1") (pinfunction "ADJ_1") (pintype "input"))
      (node (ref "M1") (pin "-") (pinfunction "-_-") (pintype "bidirectional"))
      (node (ref "M10") (pin "-") (pinfunction "-_-") (pintype "bidirectional"))
      (node (ref "M11") (pin "-") (pinfunction "-_-") (pintype "bidirectional"))
      (node (ref "M12") (pin "-") (pinfunction "-_-") (pintype "bidirectional"))
      (node (ref "M13") (pin "-") (pinfunction "-_-") (pintype "bidirectional"))
      (node (ref "M14") (pin "-") (pinfunction "-_-") (pintype "bidirectional"))
      (node (ref "M15") (pin "-") (pinfunction "-_-") (pintype "bidirectional"))
      (node (ref "M2") (pin "-") (pinfunction "-_-") (pintype "bidirectional"))
      (node (ref "M3") (pin "-") (pinfunction "-_-") (pintype "bidirectional"))
      (node (ref "M4") (pin "-") (pinfunction "-_-") (pintype "bidirectional"))
      (node (ref "M5") (pin "-") (pinfunction "-_-") (pintype "bidirectional"))
      (node (ref "M6") (pin "-") (pinfunction "-_-") (pintype "bidirectional"))
      (node (ref "M7") (pin "-") (pinfunction "-_-") (pintype "bidirectional"))
      (node (ref "M8") (pin "-") (pinfunction "-_-") (pintype "bidirectional"))
      (node (ref "M9") (pin "-") (pinfunction "-_-") (pintype "bidirectional"))
      (node (ref "R23") (pin "P$1") (pinfunction "1_P$1") (pintype "passive"))
      (node (ref "U1") (pin "13") (pinfunction "G_13") (pintype "input"))
      (node (ref "U1") (pin "8") (pinfunction "GND_8") (pintype "power_in"))
      (node (ref "U2") (pin "13") (pinfunction "G_13") (pintype "input"))
      (node (ref "U2") (pin "8") (pinfunction "GND_8") (pintype "power_in"))
      (node (ref "U3") (pin "18") (pinfunction "GND_18") (pintype "power_in"))
    )
    (net (code "35") (name "Net-(IC1-IN)") (class "Default")
      (node (ref "BT2") (pin "+") (pinfunction "+_+") (pintype "power_in"))
      (node (ref "C10") (pin "1") (pinfunction "1_1") (pintype "passive"))
      (node (ref "IC1") (pin "3") (pinfunction "IN_3") (pintype "input"))
    )
    (net (code "36") (name "Net-(Q1-B)") (class "Default")
      (node (ref "Q1") (pin "2") (pinfunction "B_2") (pintype "passive"))
      (node (ref "R21") (pin "P$1") (pinfunction "1_P$1") (pintype "passive"))
    )
    (net (code "37") (name "Net-(Q1-E)") (class "Default")
      (node (ref "D14") (pin "A") (pinfunction "A_A") (pintype "passive"))
      (node (ref "Q1") (pin "1") (pinfunction "E_1") (pintype "passive"))
    )
    (net (code "38") (name "Net-(Q2-B)") (class "Default")
      (node (ref "Q2") (pin "2") (pinfunction "B_2") (pintype "passive"))
      (node (ref "R22") (pin "P$1") (pinfunction "1_P$1") (pintype "passive"))
    )
    (net (code "39") (name "Net-(Q2-E)") (class "Default")
      (node (ref "D15") (pin "A") (pinfunction "A_A") (pintype "passive"))
      (node (ref "Q2") (pin "1") (pinfunction "E_1") (pintype "passive"))
    )
    (net (code "40") (name "Net-(R1-1)") (class "Default")
      (node (ref "R1") (pin "P$1") (pinfunction "1_P$1") (pintype "passive"))
      (node (ref "U1") (pin "15") (pinfunction "QA_15") (pintype "tri_state"))
    )
    (net (code "41") (name "Net-(R1-2)") (class "Default")
      (node (ref "R1") (pin "P$2") (pinfunction "2_P$2") (pintype "passive"))
      (node (ref "T1") (pin "B") (pinfunction "B_B") (pintype "passive"))
    )
    (net (code "42") (name "Net-(R2-1)") (class "Default")
      (node (ref "R2") (pin "P$1") (pinfunction "1_P$1") (pintype "passive"))
      (node (ref "U1") (pin "1") (pinfunction "QB_1") (pintype "tri_state"))
    )
    (net (code "43") (name "Net-(R2-2)") (class "Default")
      (node (ref "R2") (pin "P$2") (pinfunction "2_P$2") (pintype "passive"))
      (node (ref "T2") (pin "B") (pinfunction "B_B") (pintype "passive"))
    )
    (net (code "44") (name "Net-(R3-1)") (class "Default")
      (node (ref "R3") (pin "P$1") (pinfunction "1_P$1") (pintype "passive"))
      (node (ref "U1") (pin "2") (pinfunction "QC_2") (pintype "tri_state"))
    )
    (net (code "45") (name "Net-(R3-2)") (class "Default")
      (node (ref "R3") (pin "P$2") (pinfunction "2_P$2") (pintype "passive"))
      (node (ref "T3") (pin "B") (pinfunction "B_B") (pintype "passive"))
    )
    (net (code "46") (name "Net-(R4-1)") (class "Default")
      (node (ref "R4") (pin "P$1") (pinfunction "1_P$1") (pintype "passive"))
      (node (ref "U1") (pin "3") (pinfunction "QD_3") (pintype "tri_state"))
    )
    (net (code "47") (name "Net-(R4-2)") (class "Default")
      (node (ref "R4") (pin "P$2") (pinfunction "2_P$2") (pintype "passive"))
      (node (ref "T4") (pin "B") (pinfunction "B_B") (pintype "passive"))
    )
    (net (code "48") (name "Net-(R5-1)") (class "Default")
      (node (ref "R5") (pin "P$1") (pinfunction "1_P$1") (pintype "passive"))
      (node (ref "U1") (pin "4") (pinfunction "QE_4") (pintype "tri_state"))
    )
    (net (code "49") (name "Net-(R5-2)") (class "Default")
      (node (ref "R5") (pin "P$2") (pinfunction "2_P$2") (pintype "passive"))
      (node (ref "T5") (pin "B") (pinfunction "B_B") (pintype "passive"))
    )
    (net (code "50") (name "Net-(R6-1)") (class "Default")
      (node (ref "R6") (pin "P$1") (pinfunction "1_P$1") (pintype "passive"))
      (node (ref "U1") (pin "5") (pinfunction "QF_5") (pintype "tri_state"))
    )
    (net (code "51") (name "Net-(R6-2)") (class "Default")
      (node (ref "R6") (pin "P$2") (pinfunction "2_P$2") (pintype "passive"))
      (node (ref "T6") (pin "B") (pinfunction "B_B") (pintype "passive"))
    )
    (net (code "52") (name "Net-(R7-1)") (class "Default")
      (node (ref "R7") (pin "P$1") (pinfunction "1_P$1") (pintype "passive"))
      (node (ref "U1") (pin "6") (pinfunction "QG_6") (pintype "tri_state"))
    )
    (net (code "53") (name "Net-(R7-2)") (class "Default")
      (node (ref "R7") (pin "P$2") (pinfunction "2_P$2") (pintype "passive"))
      (node (ref "T7") (pin "B") (pinfunction "B_B") (pintype "passive"))
    )
    (net (code "54") (name "Net-(R8-1)") (class "Default")
      (node (ref "R8") (pin "P$1") (pinfunction "1_P$1") (pintype "passive"))
      (node (ref "U1") (pin "7") (pinfunction "QH_7") (pintype "tri_state"))
    )
    (net (code "55") (name "Net-(R8-2)") (class "Default")
      (node (ref "R8") (pin "P$2") (pinfunction "2_P$2") (pintype "passive"))
      (node (ref "T8") (pin "B") (pinfunction "B_B") (pintype "passive"))
    )
    (net (code "56") (name "Net-(R9-1)") (class "Default")
      (node (ref "R9") (pin "P$1") (pinfunction "1_P$1") (pintype "passive"))
      (node (ref "U2") (pin "15") (pinfunction "QA_15") (pintype "tri_state"))
    )
    (net (code "57") (name "Net-(R9-2)") (class "Default")
      (node (ref "R9") (pin "P$2") (pinfunction "2_P$2") (pintype "passive"))
      (node (ref "T9") (pin "B") (pinfunction "B_B") (pintype "passive"))
    )
    (net (code "58") (name "Net-(R10-1)") (class "Default")
      (node (ref "R10") (pin "P$1") (pinfunction "1_P$1") (pintype "passive"))
      (node (ref "U2") (pin "1") (pinfunction "QB_1") (pintype "tri_state"))
    )
    (net (code "59") (name "Net-(R10-2)") (class "Default")
      (node (ref "R10") (pin "P$2") (pinfunction "2_P$2") (pintype "passive"))
      (node (ref "T10") (pin "B") (pinfunction "B_B") (pintype "passive"))
    )
    (net (code "60") (name "Net-(R11-1)") (class "Default")
      (node (ref "R11") (pin "P$1") (pinfunction "1_P$1") (pintype "passive"))
      (node (ref "U2") (pin "2") (pinfunction "QC_2") (pintype "tri_state"))
    )
    (net (code "61") (name "Net-(R11-2)") (class "Default")
      (node (ref "R11") (pin "P$2") (pinfunction "2_P$2") (pintype "passive"))
      (node (ref "T11") (pin "B") (pinfunction "B_B") (pintype "passive"))
    )
    (net (code "62") (name "Net-(R12-1)") (class "Default")
      (node (ref "R12") (pin "P$1") (pinfunction "1_P$1") (pintype "passive"))
      (node (ref "U2") (pin "3") (pinfunction "QD_3") (pintype "tri_state"))
    )
    (net (code "63") (name "Net-(R12-2)") (class "Default")
      (node (ref "R12") (pin "P$2") (pinfunction "2_P$2") (pintype "passive"))
      (node (ref "T12") (pin "B") (pinfunction "B_B") (pintype "passive"))
    )
    (net (code "64") (name "Net-(R13-1)") (class "Default")
      (node (ref "R13") (pin "P$1") (pinfunction "1_P$1") (pintype "passive"))
      (node (ref "U2") (pin "4") (pinfunction "QE_4") (pintype "tri_state"))
    )
    (net (code "65") (name "Net-(R13-2)") (class "Default")
      (node (ref "R13") (pin "P$2") (pinfunction "2_P$2") (pintype "passive"))
      (node (ref "T13") (pin "B") (pinfunction "B_B") (pintype "passive"))
    )
    (net (code "66") (name "Net-(R14-1)") (class "Default")
      (node (ref "R14") (pin "P$1") (pinfunction "1_P$1") (pintype "passive"))
      (node (ref "U2") (pin "5") (pinfunction "QF_5") (pintype "tri_state"))
    )
    (net (code "67") (name "Net-(R14-2)") (class "Default")
      (node (ref "R14") (pin "P$2") (pinfunction "2_P$2") (pintype "passive"))
      (node (ref "T14") (pin "B") (pinfunction "B_B") (pintype "passive"))
    )
    (net (code "68") (name "Net-(R15-1)") (class "Default")
      (node (ref "R15") (pin "P$1") (pinfunction "1_P$1") (pintype "passive"))
      (node (ref "U2") (pin "6") (pinfunction "QG_6") (pintype "tri_state"))
    )
    (net (code "69") (name "Net-(R15-2)") (class "Default")
      (node (ref "R15") (pin "P$2") (pinfunction "2_P$2") (pintype "passive"))
      (node (ref "T15") (pin "B") (pinfunction "B_B") (pintype "passive"))
    )
    (net (code "70") (name "Net-(R16-1)") (class "Default")
      (node (ref "D9") (pin "A") (pinfunction "A_A") (pintype "passive"))
      (node (ref "R16") (pin "P$1") (pinfunction "1_P$1") (pintype "passive"))
    )
    (net (code "71") (name "Net-(R16-2)") (class "Default")
      (node (ref "J2") (pin "5") (pinfunction "5_5") (pintype "passive"))
      (node (ref "R16") (pin "P$2") (pinfunction "2_P$2") (pintype "passive"))
    )
    (net (code "72") (name "Net-(R17-1)") (class "Default")
      (node (ref "D10") (pin "A") (pinfunction "A_A") (pintype "passive"))
      (node (ref "R17") (pin "P$1") (pinfunction "1_P$1") (pintype "passive"))
    )
    (net (code "73") (name "Net-(R17-2)") (class "Default")
      (node (ref "J2") (pin "4") (pinfunction "4_4") (pintype "passive"))
      (node (ref "R17") (pin "P$2") (pinfunction "2_P$2") (pintype "passive"))
    )
    (net (code "74") (name "Net-(R18-1)") (class "Default")
      (node (ref "D11") (pin "A") (pinfunction "A_A") (pintype "passive"))
      (node (ref "R18") (pin "P$1") (pinfunction "1_P$1") (pintype "passive"))
    )
    (net (code "75") (name "Net-(R18-2)") (class "Default")
      (node (ref "J2") (pin "3") (pinfunction "3_3") (pintype "passive"))
      (node (ref "R18") (pin "P$2") (pinfunction "2_P$2") (pintype "passive"))
    )
    (net (code "76") (name "Net-(R19-1)") (class "Default")
      (node (ref "D12") (pin "A") (pinfunction "A_A") (pintype "passive"))
      (node (ref "R19") (pin "P$1") (pinfunction "1_P$1") (pintype "passive"))
    )
    (net (code "77") (name "Net-(R19-2)") (class "Default")
      (node (ref "J2") (pin "2") (pinfunction "2_2") (pintype "passive"))
      (node (ref "R19") (pin "P$2") (pinfunction "2_P$2") (pintype "passive"))
    )
    (net (code "78") (name "Net-(R20-1)") (class "Default")
      (node (ref "D13") (pin "A") (pinfunction "A_A") (pintype "passive"))
      (node (ref "R20") (pin "P$1") (pinfunction "1_P$1") (pintype "passive"))
    )
    (net (code "79") (name "Net-(R20-2)") (class "Default")
      (node (ref "J2") (pin "1") (pinfunction "1_1") (pintype "passive"))
      (node (ref "R20") (pin "P$2") (pinfunction "2_P$2") (pintype "passive"))
    )
    (net (code "80") (name "Net-(U1-RCK)") (class "Default")
      (node (ref "C11") (pin "1") (pinfunction "1_1") (pintype "passive"))
      (node (ref "INPUT") (pin "3") (pinfunction "3_3") (pintype "passive"))
      (node (ref "OUTPUT") (pin "3") (pinfunction "3_3") (pintype "passive"))
      (node (ref "U1") (pin "12") (pinfunction "RCK_12") (pintype "input"))
    )
    (net (code "81") (name "Net-(U1-SCK)") (class "Default")
      (node (ref "INPUT") (pin "2") (pinfunction "2_2") (pintype "passive"))
      (node (ref "OUTPUT") (pin "2") (pinfunction "2_2") (pintype "passive"))
      (node (ref "U1") (pin "11") (pinfunction "SCK_11") (pintype "input"))
    )
    (net (code "82") (name "Net-(U1-SER)") (class "Default")
      (node (ref "INPUT") (pin "1") (pinfunction "1_1") (pintype "passive"))
      (node (ref "U1") (pin "14") (pinfunction "SER_14") (pintype "input"))
    )
    (net (code "83") (name "Net-(U2-RCK)") (class "Default")
      (node (ref "C9") (pin "1") (pinfunction "1_1") (pintype "passive"))
      (node (ref "INPUT1") (pin "3") (pinfunction "3_3") (pintype "passive"))
      (node (ref "OUTPUT1") (pin "3") (pinfunction "3_3") (pintype "passive"))
      (node (ref "U2") (pin "12") (pinfunction "RCK_12") (pintype "input"))
    )
    (net (code "84") (name "Net-(U2-SCK)") (class "Default")
      (node (ref "INPUT1") (pin "2") (pinfunction "2_2") (pintype "passive"))
      (node (ref "OUTPUT1") (pin "2") (pinfunction "2_2") (pintype "passive"))
      (node (ref "U2") (pin "11") (pinfunction "SCK_11") (pintype "input"))
    )
    (net (code "85") (name "Net-(U2-SER)") (class "Default")
      (node (ref "INPUT1") (pin "1") (pinfunction "1_1") (pintype "passive"))
      (node (ref "U2") (pin "14") (pinfunction "SER_14") (pintype "input"))
    )
    (net (code "86") (name "Net-(U3-INT)") (class "Default")
      (node (ref "B1") (pin "D2") (pinfunction "D2_D2") (pintype "bidirectional"))
      (node (ref "U3") (pin "12") (pinfunction "INT_12") (pintype "output"))
    )
    (net (code "87") (name "Net-(U3-SCL)") (class "Default")
      (node (ref "B1") (pin "A5") (pinfunction "A5_A5") (pintype "bidirectional"))
      (node (ref "U3") (pin "23") (pinfunction "SCL_23") (pintype "bidirectional"))
    )
    (net (code "88") (name "Net-(U3-SDA)") (class "Default")
      (node (ref "B1") (pin "A4") (pinfunction "A4_A4") (pintype "bidirectional"))
      (node (ref "U3") (pin "24") (pinfunction "SDA_24") (pintype "bidirectional"))
    )
    (net (code "89") (name "VCC") (class "Default")
      (node (ref "U1") (pin "10") (pinfunction "SCL_10") (pintype "input"))
      (node (ref "U1") (pin "16") (pinfunction "VCC_16") (pintype "power_in"))
      (node (ref "U2") (pin "10") (pinfunction "SCL_10") (pintype "input"))
      (node (ref "U2") (pin "16") (pinfunction "VCC_16") (pintype "power_in"))
    )
    (net (code "90") (name "unconnected-(B1-GND-PadGND@1)") (class "Default")
      (node (ref "B1") (pin "GND@1") (pinfunction "GND_GND@1") (pintype "bidirectional"))
    )
    (net (code "91") (name "unconnected-(B1-GND-PadGND@2)") (class "Default")
      (node (ref "B1") (pin "GND@2") (pinfunction "GND_GND@2") (pintype "bidirectional"))
    )
    (net (code "92") (name "unconnected-(B1-GND-PadGND@3)") (class "Default")
      (node (ref "B1") (pin "GND@3") (pinfunction "GND_GND@3") (pintype "bidirectional"))
    )
    (net (code "93") (name "unconnected-(B1-GND-PadGND@4)") (class "Default")
      (node (ref "B1") (pin "GND@4") (pinfunction "GND_GND@4") (pintype "bidirectional"))
    )
    (net (code "94") (name "unconnected-(B1-Pad3.3V)") (class "Default")
      (node (ref "B1") (pin "3.3V") (pinfunction "3.3V_3.3V") (pintype "bidirectional"))
    )
    (net (code "95") (name "unconnected-(B1-PadA1)") (class "Default")
      (node (ref "B1") (pin "A1") (pinfunction "A1_A1") (pintype "bidirectional"))
    )
    (net (code "96") (name "unconnected-(B1-PadA2)") (class "Default")
      (node (ref "B1") (pin "A2") (pinfunction "A2_A2") (pintype "bidirectional"))
    )
    (net (code "97") (name "unconnected-(B1-PadA3)") (class "Default")
      (node (ref "B1") (pin "A3") (pinfunction "A3_A3") (pintype "bidirectional"))
    )
    (net (code "98") (name "unconnected-(B1-PadAREF)") (class "Default")
      (node (ref "B1") (pin "AREF") (pinfunction "AREF_AREF") (pintype "bidirectional"))
    )
    (net (code "99") (name "unconnected-(B1-PadD0)") (class "Default")
      (node (ref "B1") (pin "D0") (pinfunction "D0_D0") (pintype "bidirectional"))
    )
    (net (code "100") (name "unconnected-(B1-PadD1)") (class "Default")
      (node (ref "B1") (pin "D1") (pinfunction "D1_D1") (pintype "bidirectional"))
    )
    (net (code "101") (name "unconnected-(B1-PadD13)") (class "Default")
      (node (ref "B1") (pin "D13") (pinfunction "D13_D13") (pintype "bidirectional"))
    )
    (net (code "102") (name "unconnected-(B1-PadIOREF)") (class "Default")
      (node (ref "B1") (pin "IOREF") (pinfunction "IOREF_IOREF") (pintype "bidirectional"))
    )
    (net (code "103") (name "unconnected-(B1-PadMISO)") (class "Default")
      (node (ref "B1") (pin "MISO") (pinfunction "MISO_MISO") (pintype "bidirectional"))
    )
    (net (code "104") (name "unconnected-(B1-PadMOSI)") (class "Default")
      (node (ref "B1") (pin "MOSI") (pinfunction "MOSI_MOSI") (pintype "bidirectional"))
    )
    (net (code "105") (name "unconnected-(B1-PadSCK)") (class "Default")
      (node (ref "B1") (pin "SCK") (pinfunction "SCK_SCK") (pintype "bidirectional"))
    )
    (net (code "106") (name "unconnected-(B1-PadSCL)") (class "Default")
      (node (ref "B1") (pin "SCL") (pinfunction "SCL_SCL") (pintype "bidirectional"))
    )
    (net (code "107") (name "unconnected-(B1-PadSDA)") (class "Default")
      (node (ref "B1") (pin "SDA") (pinfunction "SDA_SDA") (pintype "bidirectional"))
    )
    (net (code "108") (name "unconnected-(B1-PadVCC)") (class "Default")
      (node (ref "B1") (pin "VCC") (pinfunction "VCC_VCC") (pintype "bidirectional"))
    )
    (net (code "109") (name "unconnected-(B1-PadVIN)") (class "Default")
      (node (ref "B1") (pin "VIN") (pinfunction "VIN_VIN") (pintype "bidirectional"))
    )
    (net (code "110") (name "unconnected-(B1-~{RESET}-PadRESET@1)") (class "Default")
      (node (ref "B1") (pin "RESET@1") (pinfunction "~{RESET}_RESET@1") (pintype "bidirectional"))
    )
    (net (code "111") (name "unconnected-(B1-~{RESET}-PadRESET@2)") (class "Default")
      (node (ref "B1") (pin "RESET@2") (pinfunction "~{RESET}_RESET@2") (pintype "bidirectional"))
    )
    (net (code "112") (name "unconnected-(J1-Pad16)") (class "Default")
      (node (ref "J1") (pin "16") (pinfunction "16_16") (pintype "passive"))
    )
    (net (code "113") (name "unconnected-(U2-QH-Pad7)") (class "Default")
      (node (ref "U2") (pin "7") (pinfunction "QH_7") (pintype "tri_state"))
    )
    (net (code "114") (name "unconnected-(U3-AD0-Pad9)") (class "Default")
      (node (ref "U3") (pin "9") (pinfunction "AD0_9") (pintype "bidirectional"))
    )
    (net (code "115") (name "unconnected-(U3-AUX_CL-Pad7)") (class "Default")
      (node (ref "U3") (pin "7") (pinfunction "AUX_CL_7") (pintype "bidirectional"))
    )
    (net (code "116") (name "unconnected-(U3-AUX_DA-Pad6)") (class "Default")
      (node (ref "U3") (pin "6") (pinfunction "AUX_DA_6") (pintype "bidirectional"))
    )
    (net (code "117") (name "unconnected-(U3-CLKIN-Pad1)") (class "Default")
      (node (ref "U3") (pin "1") (pinfunction "CLKIN_1") (pintype "input"))
    )
    (net (code "118") (name "unconnected-(U3-CPOUT-Pad20)") (class "Default")
      (node (ref "U3") (pin "20") (pinfunction "CPOUT_20") (pintype "output"))
    )
    (net (code "119") (name "unconnected-(U3-FSYNC-Pad11)") (class "Default")
      (node (ref "U3") (pin "11") (pinfunction "FSYNC_11") (pintype "input"))
    )
    (net (code "120") (name "unconnected-(U3-NC_2-Pad2)") (class "Default")
      (node (ref "U3") (pin "2") (pinfunction "NC_2_2") (pintype "passive"))
    )
    (net (code "121") (name "unconnected-(U3-NC_3-Pad3)") (class "Default")
      (node (ref "U3") (pin "3") (pinfunction "NC_3_3") (pintype "passive"))
    )
    (net (code "122") (name "unconnected-(U3-NC_4-Pad4)") (class "Default")
      (node (ref "U3") (pin "4") (pinfunction "NC_4_4") (pintype "passive"))
    )
    (net (code "123") (name "unconnected-(U3-NC_5-Pad5)") (class "Default")
      (node (ref "U3") (pin "5") (pinfunction "NC_5_5") (pintype "passive"))
    )
    (net (code "124") (name "unconnected-(U3-NC_14-Pad14)") (class "Default")
      (node (ref "U3") (pin "14") (pinfunction "NC_14_14") (pintype "passive"))
    )
    (net (code "125") (name "unconnected-(U3-NC_15-Pad15)") (class "Default")
      (node (ref "U3") (pin "15") (pinfunction "NC_15_15") (pintype "passive"))
    )
    (net (code "126") (name "unconnected-(U3-NC_16-Pad16)") (class "Default")
      (node (ref "U3") (pin "16") (pinfunction "NC_16_16") (pintype "passive"))
    )
    (net (code "127") (name "unconnected-(U3-NC_17-Pad17)") (class "Default")
      (node (ref "U3") (pin "17") (pinfunction "NC_17_17") (pintype "passive"))
    )
    (net (code "128") (name "unconnected-(U3-REGOUT-Pad10)") (class "Default")
      (node (ref "U3") (pin "10") (pinfunction "REGOUT_10") (pintype "passive"))
    )
    (net (code "129") (name "unconnected-(U3-RESV_19-Pad19)") (class "Default")
      (node (ref "U3") (pin "19") (pinfunction "RESV_19_19") (pintype "passive"))
    )
    (net (code "130") (name "unconnected-(U3-RESV_21-Pad21)") (class "Default")
      (node (ref "U3") (pin "21") (pinfunction "RESV_21_21") (pintype "passive"))
    )
    (net (code "131") (name "unconnected-(U3-RESV_22-Pad22)") (class "Default")
      (node (ref "U3") (pin "22") (pinfunction "RESV_22_22") (pintype "passive"))
    )
  )
)
